# FPGA_IO.net
KiCad netlist of a schematic drawn in Altium Designer
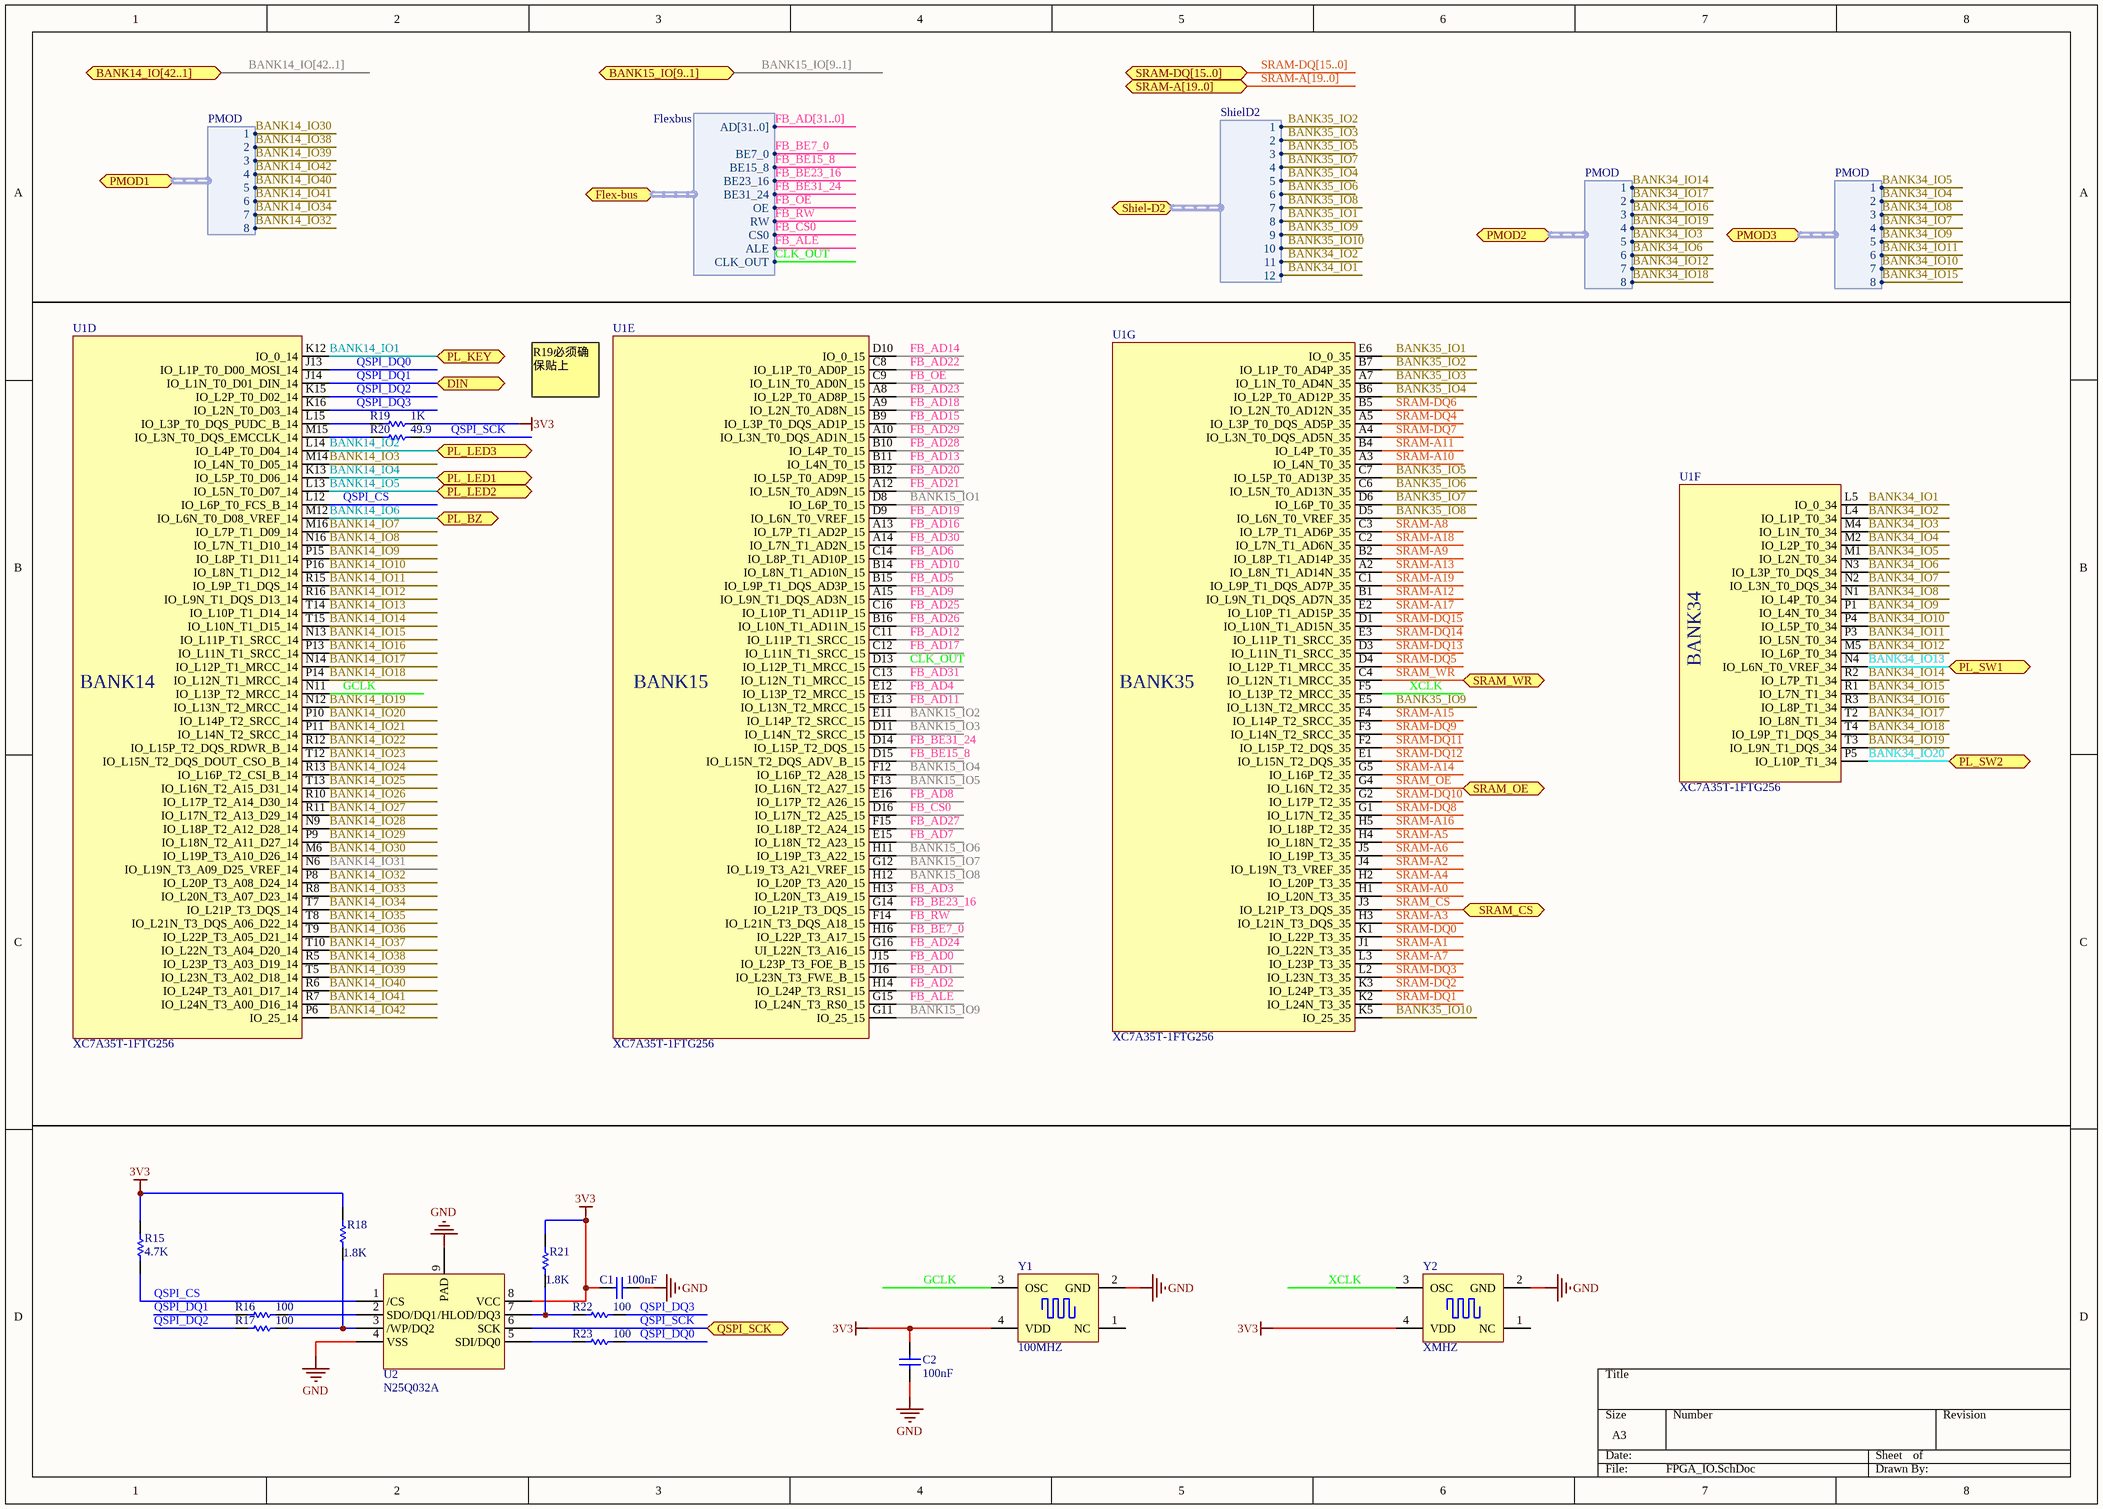
[diagram p0: FPGA_IO.SchDoc]

(export (version "E")
  (design (tool "Eeschema 10.0.6"))
  (components
    (comp (ref "C1")
      (value "100nF")
      (footprint "1608[0603]")
      (description "贴片电容")
      (fields (field (name "Comment") "Cap") (field (name "PUBLISHER") "Altium Limited"))
      (libsource (lib "Sparks") (part "Cap"))
    )
    (comp (ref "C2")
      (value "100nF")
      (footprint "1608[0603]")
      (description "贴片电容")
      (fields (field (name "Comment") "Cap") (field (name "PUBLISHER") "Altium Limited"))
      (libsource (lib "Sparks") (part "Cap"))
    )
    (comp (ref "R15")
      (value "4.7K")
      (footprint "1608[0603]")
      (description "贴片电阻")
      (fields (field (name "Comment") "Res") (field (name "PUBLISHER") "Altium Limited"))
      (libsource (lib "Sparks") (part "Res"))
    )
    (comp (ref "R16")
      (value "100")
      (footprint "1608[0603]")
      (description "贴片电阻")
      (fields (field (name "Comment") "Res") (field (name "PUBLISHER") "Altium Limited"))
      (libsource (lib "Sparks") (part "Res"))
    )
    (comp (ref "R17")
      (value "100")
      (footprint "1608[0603]")
      (description "贴片电阻")
      (fields (field (name "Comment") "Res") (field (name "PUBLISHER") "Altium Limited"))
      (libsource (lib "Sparks") (part "Res"))
    )
    (comp (ref "R18")
      (value "1.8K")
      (footprint "1608[0603]")
      (description "贴片电阻")
      (fields (field (name "Comment") "Res") (field (name "PUBLISHER") "Altium Limited"))
      (libsource (lib "Sparks") (part "Res"))
    )
    (comp (ref "R19")
      (value "1K")
      (footprint "1608[0603]")
      (description "贴片电阻")
      (fields (field (name "Comment") "Res") (field (name "PUBLISHER") "Altium Limited"))
      (libsource (lib "Sparks") (part "Res"))
    )
    (comp (ref "R20")
      (value "49.9")
      (footprint "R2012")
      (description "贴片电阻")
      (fields (field (name "Comment") "Res") (field (name "PUBLISHER") "Altium Limited"))
      (libsource (lib "Sparks") (part "Res"))
    )
    (comp (ref "R21")
      (value "1.8K")
      (footprint "1608[0603]")
      (description "贴片电阻")
      (fields (field (name "Comment") "Res") (field (name "PUBLISHER") "Altium Limited"))
      (libsource (lib "Sparks") (part "Res"))
    )
    (comp (ref "R22")
      (value "100")
      (footprint "1608[0603]")
      (description "贴片电阻")
      (fields (field (name "Comment") "Res") (field (name "PUBLISHER") "Altium Limited"))
      (libsource (lib "Sparks") (part "Res"))
    )
    (comp (ref "R23")
      (value "100")
      (footprint "R2012")
      (description "贴片电阻")
      (fields (field (name "Comment") "Res") (field (name "PUBLISHER") "Altium Limited"))
      (libsource (lib "Sparks") (part "Res"))
    )
    (comp (ref "U1")
      (value "XC7A35T-1FTG256")
      (footprint "BGA100P9X9-81A")
      (libsource (lib "Schlib") (part "XC7A35T-1FTG256"))
    )
    (comp (ref "U2")
      (value "N25Q032A")
      (footprint "QFN127P500X600X100_HS-9N")
      (libsource (lib "2号库") (part "N25Q032A"))
    )
    (comp (ref "Y1") (value "100MHZ") (footprint "XTAL7_3225") (libsource (lib "K60-V4.0") (part "XTAL1")))
    (comp (ref "Y2") (value "XMHZ") (footprint "XTAL7_3225") (libsource (lib "K60-V4.0") (part "XTAL1")))
  )
  (nets
    (net (code "4") (name "/BANK14_IO1") (class "Default")
      (node (ref "U1") (pin "K12") (pinfunction "IO_0_14_K12") (pintype "passive"))
    )
    (net (code "5") (name "/BANK14_IO2") (class "Default")
      (node (ref "U1") (pin "L14") (pinfunction "IO_L4P_T0_D04_14_L14") (pintype "passive"))
    )
    (net (code "6") (name "/BANK14_IO3") (class "Default")
      (node (ref "U1") (pin "M14") (pinfunction "IO_L4N_T0_D05_14_M14") (pintype "passive"))
    )
    (net (code "7") (name "/BANK14_IO4") (class "Default")
      (node (ref "U1") (pin "K13") (pinfunction "IO_L5P_T0_D06_14_K13") (pintype "passive"))
    )
    (net (code "8") (name "/BANK14_IO5") (class "Default")
      (node (ref "U1") (pin "L13") (pinfunction "IO_L5N_T0_D07_14_L13") (pintype "passive"))
    )
    (net (code "9") (name "/BANK14_IO6") (class "Default")
      (node (ref "U1") (pin "M12") (pinfunction "IO_L6N_T0_D08_VREF_14_M12") (pintype "passive"))
    )
    (net (code "10") (name "/BANK14_IO7") (class "Default")
      (node (ref "U1") (pin "M16") (pinfunction "IO_L7P_T1_D09_14_M16") (pintype "passive"))
    )
    (net (code "11") (name "/BANK14_IO8") (class "Default")
      (node (ref "U1") (pin "N16") (pinfunction "IO_L7N_T1_D10_14_N16") (pintype "passive"))
    )
    (net (code "12") (name "/BANK14_IO9") (class "Default")
      (node (ref "U1") (pin "P15") (pinfunction "IO_L8P_T1_D11_14_P15") (pintype "passive"))
    )
    (net (code "13") (name "/BANK14_IO10") (class "Default")
      (node (ref "U1") (pin "P16") (pinfunction "IO_L8N_T1_D12_14_P16") (pintype "passive"))
    )
    (net (code "14") (name "/BANK14_IO11") (class "Default")
      (node (ref "U1") (pin "R15") (pinfunction "IO_L9P_T1_DQS_14_R15") (pintype "passive"))
    )
    (net (code "15") (name "/BANK14_IO12") (class "Default")
      (node (ref "U1") (pin "R16") (pinfunction "IO_L9N_T1_DQS_D13_14_R16") (pintype "passive"))
    )
    (net (code "16") (name "/BANK14_IO13") (class "Default")
      (node (ref "U1") (pin "T14") (pinfunction "IO_L10P_T1_D14_14_T14") (pintype "passive"))
    )
    (net (code "17") (name "/BANK14_IO14") (class "Default")
      (node (ref "U1") (pin "T15") (pinfunction "IO_L10N_T1_D15_14_T15") (pintype "passive"))
    )
    (net (code "18") (name "/BANK14_IO15") (class "Default")
      (node (ref "U1") (pin "N13") (pinfunction "IO_L11P_T1_SRCC_14_N13") (pintype "passive"))
    )
    (net (code "19") (name "/BANK14_IO16") (class "Default")
      (node (ref "U1") (pin "P13") (pinfunction "IO_L11N_T1_SRCC_14_P13") (pintype "passive"))
    )
    (net (code "20") (name "/BANK14_IO17") (class "Default")
      (node (ref "U1") (pin "N14") (pinfunction "IO_L12P_T1_MRCC_14_N14") (pintype "passive"))
    )
    (net (code "21") (name "/BANK14_IO18") (class "Default")
      (node (ref "U1") (pin "P14") (pinfunction "IO_L12N_T1_MRCC_14_P14") (pintype "passive"))
    )
    (net (code "22") (name "/BANK14_IO19") (class "Default")
      (node (ref "U1") (pin "N12") (pinfunction "IO_L13N_T2_MRCC_14_N12") (pintype "passive"))
    )
    (net (code "23") (name "/BANK14_IO20") (class "Default")
      (node (ref "U1") (pin "P10") (pinfunction "IO_L14P_T2_SRCC_14_P10") (pintype "passive"))
    )
    (net (code "24") (name "/BANK14_IO21") (class "Default")
      (node (ref "U1") (pin "P11") (pinfunction "IO_L14N_T2_SRCC_14_P11") (pintype "passive"))
    )
    (net (code "25") (name "/BANK14_IO22") (class "Default")
      (node (ref "U1") (pin "R12") (pinfunction "IO_L15P_T2_DQS_RDWR_B_14_R12") (pintype "passive"))
    )
    (net (code "26") (name "/BANK14_IO23") (class "Default")
      (node (ref "U1") (pin "T12") (pinfunction "IO_L15N_T2_DQS_DOUT_CSO_B_14_T12") (pintype "passive"))
    )
    (net (code "27") (name "/BANK14_IO24") (class "Default")
      (node (ref "U1") (pin "R13") (pinfunction "IO_L16P_T2_CSI_B_14_R13") (pintype "passive"))
    )
    (net (code "28") (name "/BANK14_IO25") (class "Default")
      (node (ref "U1") (pin "T13") (pinfunction "IO_L16N_T2_A15_D31_14_T13") (pintype "passive"))
    )
    (net (code "29") (name "/BANK14_IO26") (class "Default")
      (node (ref "U1") (pin "R10") (pinfunction "IO_L17P_T2_A14_D30_14_R10") (pintype "passive"))
    )
    (net (code "30") (name "/BANK14_IO27") (class "Default")
      (node (ref "U1") (pin "R11") (pinfunction "IO_L17N_T2_A13_D29_14_R11") (pintype "passive"))
    )
    (net (code "31") (name "/BANK14_IO28") (class "Default")
      (node (ref "U1") (pin "N9") (pinfunction "IO_L18P_T2_A12_D28_14_N9") (pintype "passive"))
    )
    (net (code "32") (name "/BANK14_IO29") (class "Default")
      (node (ref "U1") (pin "P9") (pinfunction "IO_L18N_T2_A11_D27_14_P9") (pintype "passive"))
    )
    (net (code "33") (name "/BANK14_IO30") (class "Default")
      (node (ref "U1") (pin "M6") (pinfunction "IO_L19P_T3_A10_D26_14_M6") (pintype "passive"))
    )
    (net (code "34") (name "/BANK14_IO31") (class "Default")
      (node (ref "U1") (pin "N6") (pinfunction "IO_L19N_T3_A09_D25_VREF_14_N6") (pintype "passive"))
    )
    (net (code "35") (name "/BANK14_IO32") (class "Default")
      (node (ref "U1") (pin "P8") (pinfunction "IO_L20P_T3_A08_D24_14_P8") (pintype "passive"))
    )
    (net (code "36") (name "/BANK14_IO33") (class "Default")
      (node (ref "U1") (pin "R8") (pinfunction "IO_L20N_T3_A07_D23_14_R8") (pintype "passive"))
    )
    (net (code "37") (name "/BANK14_IO34") (class "Default")
      (node (ref "U1") (pin "T7") (pinfunction "IO_L21P_T3_DQS_14_T7") (pintype "passive"))
    )
    (net (code "38") (name "/BANK14_IO35") (class "Default")
      (node (ref "U1") (pin "T8") (pinfunction "IO_L21N_T3_DQS_A06_D22_14_T8") (pintype "passive"))
    )
    (net (code "39") (name "/BANK14_IO36") (class "Default")
      (node (ref "U1") (pin "T9") (pinfunction "IO_L22P_T3_A05_D21_14_T9") (pintype "passive"))
    )
    (net (code "40") (name "/BANK14_IO37") (class "Default")
      (node (ref "U1") (pin "T10") (pinfunction "IO_L22N_T3_A04_D20_14_T10") (pintype "passive"))
    )
    (net (code "41") (name "/BANK14_IO38") (class "Default")
      (node (ref "U1") (pin "R5") (pinfunction "IO_L23P_T3_A03_D19_14_R5") (pintype "passive"))
    )
    (net (code "42") (name "/BANK14_IO39") (class "Default")
      (node (ref "U1") (pin "T5") (pinfunction "IO_L23N_T3_A02_D18_14_T5") (pintype "passive"))
    )
    (net (code "43") (name "/BANK14_IO40") (class "Default")
      (node (ref "U1") (pin "R6") (pinfunction "IO_L24P_T3_A01_D17_14_R6") (pintype "passive"))
    )
    (net (code "44") (name "/BANK14_IO41") (class "Default")
      (node (ref "U1") (pin "R7") (pinfunction "IO_L24N_T3_A00_D16_14_R7") (pintype "passive"))
    )
    (net (code "45") (name "/BANK14_IO42") (class "Default")
      (node (ref "U1") (pin "P6") (pinfunction "IO_25_14_P6") (pintype "passive"))
    )
    (net (code "47") (name "/BANK15_IO1") (class "Default")
      (node (ref "U1") (pin "D8") (pinfunction "IO_L6P_T0_15_D8") (pintype "passive"))
    )
    (net (code "48") (name "/BANK15_IO2") (class "Default")
      (node (ref "U1") (pin "E11") (pinfunction "IO_L14P_T2_SRCC_15_E11") (pintype "passive"))
    )
    (net (code "49") (name "/BANK15_IO3") (class "Default")
      (node (ref "U1") (pin "D11") (pinfunction "IO_L14N_T2_SRCC_15_D11") (pintype "passive"))
    )
    (net (code "50") (name "/BANK15_IO4") (class "Default")
      (node (ref "U1") (pin "F12") (pinfunction "IO_L16P_T2_A28_15_F12") (pintype "passive"))
    )
    (net (code "51") (name "/BANK15_IO5") (class "Default")
      (node (ref "U1") (pin "F13") (pinfunction "IO_L16N_T2_A27_15_F13") (pintype "passive"))
    )
    (net (code "52") (name "/BANK15_IO6") (class "Default")
      (node (ref "U1") (pin "H11") (pinfunction "IO_L19P_T3_A22_15_H11") (pintype "passive"))
    )
    (net (code "53") (name "/BANK15_IO7") (class "Default")
      (node (ref "U1") (pin "G12") (pinfunction "IO_L19_T3_A21_VREF_15_G12") (pintype "passive"))
    )
    (net (code "54") (name "/BANK15_IO8") (class "Default")
      (node (ref "U1") (pin "H12") (pinfunction "IO_L20P_T3_A20_15_H12") (pintype "passive"))
    )
    (net (code "55") (name "/BANK15_IO9") (class "Default")
      (node (ref "U1") (pin "G11") (pinfunction "IO_25_15_G11") (pintype "passive"))
    )
    (net (code "57") (name "/BANK34_IO1") (class "Default")
      (node (ref "U1") (pin "L5") (pinfunction "IO_0_34_L5") (pintype "passive"))
    )
    (net (code "58") (name "/BANK34_IO2") (class "Default")
      (node (ref "U1") (pin "L4") (pinfunction "IO_L1P_T0_34_L4") (pintype "passive"))
    )
    (net (code "59") (name "/BANK34_IO3") (class "Default")
      (node (ref "U1") (pin "M4") (pinfunction "IO_L1N_T0_34_M4") (pintype "passive"))
    )
    (net (code "60") (name "/BANK34_IO4") (class "Default")
      (node (ref "U1") (pin "M2") (pinfunction "IO_L2P_T0_34_M2") (pintype "passive"))
    )
    (net (code "61") (name "/BANK34_IO5") (class "Default")
      (node (ref "U1") (pin "M1") (pinfunction "IO_L2N_T0_34_M1") (pintype "passive"))
    )
    (net (code "62") (name "/BANK34_IO6") (class "Default")
      (node (ref "U1") (pin "N3") (pinfunction "IO_L3P_T0_DQS_34_N3") (pintype "passive"))
    )
    (net (code "63") (name "/BANK34_IO7") (class "Default")
      (node (ref "U1") (pin "N2") (pinfunction "IO_L3N_T0_DQS_34_N2") (pintype "passive"))
    )
    (net (code "64") (name "/BANK34_IO8") (class "Default")
      (node (ref "U1") (pin "N1") (pinfunction "IO_L4P_T0_34_N1") (pintype "passive"))
    )
    (net (code "65") (name "/BANK34_IO9") (class "Default")
      (node (ref "U1") (pin "P1") (pinfunction "IO_L4N_T0_34_P1") (pintype "passive"))
    )
    (net (code "66") (name "/BANK34_IO10") (class "Default")
      (node (ref "U1") (pin "P4") (pinfunction "IO_L5P_T0_34_P4") (pintype "passive"))
    )
    (net (code "67") (name "/BANK34_IO11") (class "Default")
      (node (ref "U1") (pin "P3") (pinfunction "IO_L5N_T0_34_P3") (pintype "passive"))
    )
    (net (code "68") (name "/BANK34_IO12") (class "Default")
      (node (ref "U1") (pin "M5") (pinfunction "IO_L6P_T0_34_M5") (pintype "passive"))
    )
    (net (code "69") (name "/BANK34_IO13") (class "Default")
      (node (ref "U1") (pin "N4") (pinfunction "IO_L6N_T0_VREF_34_N4") (pintype "passive"))
    )
    (net (code "70") (name "/BANK34_IO14") (class "Default")
      (node (ref "U1") (pin "R2") (pinfunction "IO_L7P_T1_34_R2") (pintype "passive"))
    )
    (net (code "71") (name "/BANK34_IO15") (class "Default")
      (node (ref "U1") (pin "R1") (pinfunction "IO_L7N_T1_34_R1") (pintype "passive"))
    )
    (net (code "72") (name "/BANK34_IO16") (class "Default")
      (node (ref "U1") (pin "R3") (pinfunction "IO_L8P_T1_34_R3") (pintype "passive"))
    )
    (net (code "73") (name "/BANK34_IO17") (class "Default")
      (node (ref "U1") (pin "T2") (pinfunction "IO_L8N_T1_34_T2") (pintype "passive"))
    )
    (net (code "74") (name "/BANK34_IO18") (class "Default")
      (node (ref "U1") (pin "T4") (pinfunction "IO_L9P_T1_DQS_34_T4") (pintype "passive"))
    )
    (net (code "75") (name "/BANK34_IO19") (class "Default")
      (node (ref "U1") (pin "T3") (pinfunction "IO_L9N_T1_DQS_34_T3") (pintype "passive"))
    )
    (net (code "76") (name "/BANK34_IO20") (class "Default")
      (node (ref "U1") (pin "P5") (pinfunction "IO_L10P_T1_34_P5") (pintype "passive"))
    )
    (net (code "77") (name "/BANK35_IO1") (class "Default")
      (node (ref "U1") (pin "E6") (pinfunction "IO_0_35_E6") (pintype "passive"))
    )
    (net (code "78") (name "/BANK35_IO2") (class "Default")
      (node (ref "U1") (pin "B7") (pinfunction "IO_L1P_T0_AD4P_35_B7") (pintype "passive"))
    )
    (net (code "79") (name "/BANK35_IO3") (class "Default")
      (node (ref "U1") (pin "A7") (pinfunction "IO_L1N_T0_AD4N_35_A7") (pintype "passive"))
    )
    (net (code "80") (name "/BANK35_IO4") (class "Default")
      (node (ref "U1") (pin "B6") (pinfunction "IO_L2P_T0_AD12P_35_B6") (pintype "passive"))
    )
    (net (code "81") (name "/BANK35_IO5") (class "Default")
      (node (ref "U1") (pin "C7") (pinfunction "IO_L5P_T0_AD13P_35_C7") (pintype "passive"))
    )
    (net (code "82") (name "/BANK35_IO6") (class "Default")
      (node (ref "U1") (pin "C6") (pinfunction "IO_L5N_T0_AD13N_35_C6") (pintype "passive"))
    )
    (net (code "83") (name "/BANK35_IO7") (class "Default")
      (node (ref "U1") (pin "D6") (pinfunction "IO_L6P_T0_35_D6") (pintype "passive"))
    )
    (net (code "84") (name "/BANK35_IO8") (class "Default")
      (node (ref "U1") (pin "D5") (pinfunction "IO_L6N_T0_VREF_35_D5") (pintype "passive"))
    )
    (net (code "85") (name "/BANK35_IO9") (class "Default")
      (node (ref "U1") (pin "E5") (pinfunction "IO_L13N_T2_MRCC_35_E5") (pintype "passive"))
    )
    (net (code "86") (name "/BANK35_IO10") (class "Default")
      (node (ref "U1") (pin "K5") (pinfunction "IO_25_35_K5") (pintype "passive"))
    )
    (net (code "87") (name "/CLK_OUT") (class "Default")
      (node (ref "U1") (pin "D13") (pinfunction "IO_L12P_T1_MRCC_15_D13") (pintype "passive"))
    )
    (net (code "88") (name "/FB_AD0") (class "Default")
      (node (ref "U1") (pin "J15") (pinfunction "IO_L23P_T3_FOE_B_15_J15") (pintype "passive"))
    )
    (net (code "89") (name "/FB_AD1") (class "Default")
      (node (ref "U1") (pin "J16") (pinfunction "IO_L23N_T3_FWE_B_15_J16") (pintype "passive"))
    )
    (net (code "90") (name "/FB_AD2") (class "Default")
      (node (ref "U1") (pin "H14") (pinfunction "IO_L24P_T3_RS1_15_H14") (pintype "passive"))
    )
    (net (code "91") (name "/FB_AD3") (class "Default")
      (node (ref "U1") (pin "H13") (pinfunction "IO_L20N_T3_A19_15_H13") (pintype "passive"))
    )
    (net (code "92") (name "/FB_AD4") (class "Default")
      (node (ref "U1") (pin "E12") (pinfunction "IO_L13P_T2_MRCC_15_E12") (pintype "passive"))
    )
    (net (code "93") (name "/FB_AD5") (class "Default")
      (node (ref "U1") (pin "B15") (pinfunction "IO_L9P_T1_DQS_AD3P_15_B15") (pintype "passive"))
    )
    (net (code "94") (name "/FB_AD6") (class "Default")
      (node (ref "U1") (pin "C14") (pinfunction "IO_L8P_T1_AD10P_15_C14") (pintype "passive"))
    )
    (net (code "95") (name "/FB_AD7") (class "Default")
      (node (ref "U1") (pin "E15") (pinfunction "IO_L18N_T2_A23_15_E15") (pintype "passive"))
    )
    (net (code "96") (name "/FB_AD8") (class "Default")
      (node (ref "U1") (pin "E16") (pinfunction "IO_L17P_T2_A26_15_E16") (pintype "passive"))
    )
    (net (code "97") (name "/FB_AD9") (class "Default")
      (node (ref "U1") (pin "A15") (pinfunction "IO_L9N_T1_DQS_AD3N_15_A15") (pintype "passive"))
    )
    (net (code "98") (name "/FB_AD10") (class "Default")
      (node (ref "U1") (pin "B14") (pinfunction "IO_L8N_T1_AD10N_15_B14") (pintype "passive"))
    )
    (net (code "99") (name "/FB_AD11") (class "Default")
      (node (ref "U1") (pin "E13") (pinfunction "IO_L13N_T2_MRCC_15_E13") (pintype "passive"))
    )
    (net (code "100") (name "/FB_AD12") (class "Default")
      (node (ref "U1") (pin "C11") (pinfunction "IO_L11P_T1_SRCC_15_C11") (pintype "passive"))
    )
    (net (code "101") (name "/FB_AD13") (class "Default")
      (node (ref "U1") (pin "B11") (pinfunction "IO_L4N_T0_15_B11") (pintype "passive"))
    )
    (net (code "102") (name "/FB_AD14") (class "Default")
      (node (ref "U1") (pin "D10") (pinfunction "IO_0_15_D10") (pintype "passive"))
    )
    (net (code "103") (name "/FB_AD15") (class "Default")
      (node (ref "U1") (pin "B9") (pinfunction "IO_L3P_T0_DQS_AD1P_15_B9") (pintype "passive"))
    )
    (net (code "104") (name "/FB_AD16") (class "Default")
      (node (ref "U1") (pin "A13") (pinfunction "IO_L7P_T1_AD2P_15_A13") (pintype "passive"))
    )
    (net (code "105") (name "/FB_AD17") (class "Default")
      (node (ref "U1") (pin "C12") (pinfunction "IO_L11N_T1_SRCC_15_C12") (pintype "passive"))
    )
    (net (code "106") (name "/FB_AD18") (class "Default")
      (node (ref "U1") (pin "A9") (pinfunction "IO_L2N_T0_AD8N_15_A9") (pintype "passive"))
    )
    (net (code "107") (name "/FB_AD19") (class "Default")
      (node (ref "U1") (pin "D9") (pinfunction "IO_L6N_T0_VREF_15_D9") (pintype "passive"))
    )
    (net (code "108") (name "/FB_AD20") (class "Default")
      (node (ref "U1") (pin "B12") (pinfunction "IO_L5P_T0_AD9P_15_B12") (pintype "passive"))
    )
    (net (code "109") (name "/FB_AD21") (class "Default")
      (node (ref "U1") (pin "A12") (pinfunction "IO_L5N_T0_AD9N_15_A12") (pintype "passive"))
    )
    (net (code "110") (name "/FB_AD22") (class "Default")
      (node (ref "U1") (pin "C8") (pinfunction "IO_L1P_T0_AD0P_15_C8") (pintype "passive"))
    )
    (net (code "111") (name "/FB_AD23") (class "Default")
      (node (ref "U1") (pin "A8") (pinfunction "IO_L2P_T0_AD8P_15_A8") (pintype "passive"))
    )
    (net (code "112") (name "/FB_AD24") (class "Default")
      (node (ref "U1") (pin "G16") (pinfunction "UI_L22N_T3_A16_15_G16") (pintype "passive"))
    )
    (net (code "113") (name "/FB_AD25") (class "Default")
      (node (ref "U1") (pin "C16") (pinfunction "IO_L10P_T1_AD11P_15_C16") (pintype "passive"))
    )
    (net (code "114") (name "/FB_AD26") (class "Default")
      (node (ref "U1") (pin "B16") (pinfunction "IO_L10N_T1_AD11N_15_B16") (pintype "passive"))
    )
    (net (code "115") (name "/FB_AD27") (class "Default")
      (node (ref "U1") (pin "F15") (pinfunction "IO_L18P_T2_A24_15_F15") (pintype "passive"))
    )
    (net (code "116") (name "/FB_AD28") (class "Default")
      (node (ref "U1") (pin "B10") (pinfunction "IO_L4P_T0_15_B10") (pintype "passive"))
    )
    (net (code "117") (name "/FB_AD29") (class "Default")
      (node (ref "U1") (pin "A10") (pinfunction "IO_L3N_T0_DQS_AD1N_15_A10") (pintype "passive"))
    )
    (net (code "118") (name "/FB_AD30") (class "Default")
      (node (ref "U1") (pin "A14") (pinfunction "IO_L7N_T1_AD2N_15_A14") (pintype "passive"))
    )
    (net (code "119") (name "/FB_AD31") (class "Default")
      (node (ref "U1") (pin "C13") (pinfunction "IO_L12N_T1_MRCC_15_C13") (pintype "passive"))
    )
    (net (code "120") (name "/FB_ALE") (class "Default")
      (node (ref "U1") (pin "G15") (pinfunction "IO_L24N_T3_RS0_15_G15") (pintype "passive"))
    )
    (net (code "121") (name "/FB_BE7_0") (class "Default")
      (node (ref "U1") (pin "H16") (pinfunction "IO_L22P_T3_A17_15_H16") (pintype "passive"))
    )
    (net (code "122") (name "/FB_BE15_8") (class "Default")
      (node (ref "U1") (pin "D15") (pinfunction "IO_L15N_T2_DQS_ADV_B_15_D15") (pintype "passive"))
    )
    (net (code "123") (name "/FB_BE23_16") (class "Default")
      (node (ref "U1") (pin "G14") (pinfunction "IO_L21P_T3_DQS_15_G14") (pintype "passive"))
    )
    (net (code "124") (name "/FB_BE31_24") (class "Default")
      (node (ref "U1") (pin "D14") (pinfunction "IO_L15P_T2_DQS_15_D14") (pintype "passive"))
    )
    (net (code "125") (name "/FB_CS0") (class "Default")
      (node (ref "U1") (pin "D16") (pinfunction "IO_L17N_T2_A25_15_D16") (pintype "passive"))
    )
    (net (code "126") (name "/FB_OE") (class "Default")
      (node (ref "U1") (pin "C9") (pinfunction "IO_L1N_T0_AD0N_15_C9") (pintype "passive"))
    )
    (net (code "127") (name "/FB_RW") (class "Default")
      (node (ref "U1") (pin "F14") (pinfunction "IO_L21N_T3_DQS_A18_15_F14") (pintype "passive"))
    )
    (net (code "129") (name "/GCLK") (class "Default")
      (node (ref "U1") (pin "N11") (pinfunction "IO_L13P_T2_MRCC_14_N11") (pintype "passive"))
      (node (ref "Y1") (pin "3") (pinfunction "OSC_3") (pintype "passive"))
    )
    (net (code "130") (name "/QSPI_CS") (class "Default")
      (node (ref "R15") (pin "2") (pinfunction "2_2") (pintype "passive"))
      (node (ref "U1") (pin "L12") (pinfunction "IO_L6P_T0_FCS_B_14_L12") (pintype "passive"))
      (node (ref "U2") (pin "1") (pinfunction "/CS_1") (pintype "passive"))
    )
    (net (code "131") (name "/QSPI_DQ0") (class "Default")
      (node (ref "R23") (pin "1") (pinfunction "1_1") (pintype "passive"))
      (node (ref "U1") (pin "J13") (pinfunction "IO_L1P_T0_D00_MOSI_14_J13") (pintype "passive"))
    )
    (net (code "132") (name "/QSPI_DQ1") (class "Default")
      (node (ref "R16") (pin "2") (pinfunction "2_2") (pintype "passive"))
      (node (ref "U1") (pin "J14") (pinfunction "IO_L1N_T0_D01_DIN_14_J14") (pintype "passive"))
    )
    (net (code "133") (name "/QSPI_DQ2") (class "Default")
      (node (ref "R17") (pin "2") (pinfunction "2_2") (pintype "passive"))
      (node (ref "U1") (pin "K15") (pinfunction "IO_L2P_T0_D02_14_K15") (pintype "passive"))
    )
    (net (code "134") (name "/QSPI_DQ3") (class "Default")
      (node (ref "R22") (pin "1") (pinfunction "1_1") (pintype "passive"))
      (node (ref "U1") (pin "K16") (pinfunction "IO_L2N_T0_D03_14_K16") (pintype "passive"))
    )
    (net (code "135") (name "/QSPI_SCK") (class "Default")
      (node (ref "R20") (pin "1") (pinfunction "1_1") (pintype "passive"))
      (node (ref "U2") (pin "6") (pinfunction "SCK_6") (pintype "passive"))
    )
    (net (code "136") (name "/SRAM-A0") (class "Default")
      (node (ref "U1") (pin "H1") (pinfunction "IO_L20N_T3_35_H1") (pintype "passive"))
    )
    (net (code "137") (name "/SRAM-A1") (class "Default")
      (node (ref "U1") (pin "J1") (pinfunction "IO_L22N_T3_35_J1") (pintype "passive"))
    )
    (net (code "138") (name "/SRAM-A2") (class "Default")
      (node (ref "U1") (pin "J4") (pinfunction "IO_L19N_T3_VREF_35_J4") (pintype "passive"))
    )
    (net (code "139") (name "/SRAM-A3") (class "Default")
      (node (ref "U1") (pin "H3") (pinfunction "IO_L21N_T3_DQS_35_H3") (pintype "passive"))
    )
    (net (code "140") (name "/SRAM-A4") (class "Default")
      (node (ref "U1") (pin "H2") (pinfunction "IO_L20P_T3_35_H2") (pintype "passive"))
    )
    (net (code "141") (name "/SRAM-A5") (class "Default")
      (node (ref "U1") (pin "H4") (pinfunction "IO_L18N_T2_35_H4") (pintype "passive"))
    )
    (net (code "142") (name "/SRAM-A6") (class "Default")
      (node (ref "U1") (pin "J5") (pinfunction "IO_L19P_T3_35_J5") (pintype "passive"))
    )
    (net (code "143") (name "/SRAM-A7") (class "Default")
      (node (ref "U1") (pin "L3") (pinfunction "IO_L23P_T3_35_L3") (pintype "passive"))
    )
    (net (code "144") (name "/SRAM-A8") (class "Default")
      (node (ref "U1") (pin "C3") (pinfunction "IO_L7P_T1_AD6P_35_C3") (pintype "passive"))
    )
    (net (code "145") (name "/SRAM-A9") (class "Default")
      (node (ref "U1") (pin "B2") (pinfunction "IO_L8P_T1_AD14P_35_B2") (pintype "passive"))
    )
    (net (code "146") (name "/SRAM-A10") (class "Default")
      (node (ref "U1") (pin "A3") (pinfunction "IO_L4N_T0_35_A3") (pintype "passive"))
    )
    (net (code "147") (name "/SRAM-A11") (class "Default")
      (node (ref "U1") (pin "B4") (pinfunction "IO_L4P_T0_35_B4") (pintype "passive"))
    )
    (net (code "148") (name "/SRAM-A12") (class "Default")
      (node (ref "U1") (pin "B1") (pinfunction "IO_L9N_T1_DQS_AD7N_35_B1") (pintype "passive"))
    )
    (net (code "149") (name "/SRAM-A13") (class "Default")
      (node (ref "U1") (pin "A2") (pinfunction "IO_L8N_T1_AD14N_35_A2") (pintype "passive"))
    )
    (net (code "150") (name "/SRAM-A14") (class "Default")
      (node (ref "U1") (pin "G5") (pinfunction "IO_L16P_T2_35_G5") (pintype "passive"))
    )
    (net (code "151") (name "/SRAM-A15") (class "Default")
      (node (ref "U1") (pin "F4") (pinfunction "IO_L14P_T2_SRCC_35_F4") (pintype "passive"))
    )
    (net (code "152") (name "/SRAM-A16") (class "Default")
      (node (ref "U1") (pin "H5") (pinfunction "IO_L18P_T2_35_H5") (pintype "passive"))
    )
    (net (code "153") (name "/SRAM-A17") (class "Default")
      (node (ref "U1") (pin "E2") (pinfunction "IO_L10P_T1_AD15P_35_E2") (pintype "passive"))
    )
    (net (code "154") (name "/SRAM-A18") (class "Default")
      (node (ref "U1") (pin "C2") (pinfunction "IO_L7N_T1_AD6N_35_C2") (pintype "passive"))
    )
    (net (code "155") (name "/SRAM-A19") (class "Default")
      (node (ref "U1") (pin "C1") (pinfunction "IO_L9P_T1_DQS_AD7P_35_C1") (pintype "passive"))
    )
    (net (code "157") (name "/SRAM-DQ0") (class "Default")
      (node (ref "U1") (pin "K1") (pinfunction "IO_L22P_T3_35_K1") (pintype "passive"))
    )
    (net (code "158") (name "/SRAM-DQ1") (class "Default")
      (node (ref "U1") (pin "K2") (pinfunction "IO_L24N_T3_35_K2") (pintype "passive"))
    )
    (net (code "159") (name "/SRAM-DQ2") (class "Default")
      (node (ref "U1") (pin "K3") (pinfunction "IO_L24P_T3_35_K3") (pintype "passive"))
    )
    (net (code "160") (name "/SRAM-DQ3") (class "Default")
      (node (ref "U1") (pin "L2") (pinfunction "IO_L23N_T3_35_L2") (pintype "passive"))
    )
    (net (code "161") (name "/SRAM-DQ4") (class "Default")
      (node (ref "U1") (pin "A5") (pinfunction "IO_L3P_T0_DQS_AD5P_35_A5") (pintype "passive"))
    )
    (net (code "162") (name "/SRAM-DQ5") (class "Default")
      (node (ref "U1") (pin "D4") (pinfunction "IO_L12P_T1_MRCC_35_D4") (pintype "passive"))
    )
    (net (code "163") (name "/SRAM-DQ6") (class "Default")
      (node (ref "U1") (pin "B5") (pinfunction "IO_L2N_T0_AD12N_35_B5") (pintype "passive"))
    )
    (net (code "164") (name "/SRAM-DQ7") (class "Default")
      (node (ref "U1") (pin "A4") (pinfunction "IO_L3N_T0_DQS_AD5N_35_A4") (pintype "passive"))
    )
    (net (code "165") (name "/SRAM-DQ8") (class "Default")
      (node (ref "U1") (pin "G1") (pinfunction "IO_L17N_T2_35_G1") (pintype "passive"))
    )
    (net (code "166") (name "/SRAM-DQ9") (class "Default")
      (node (ref "U1") (pin "F3") (pinfunction "IO_L14N_T2_SRCC_35_F3") (pintype "passive"))
    )
    (net (code "167") (name "/SRAM-DQ10") (class "Default")
      (node (ref "U1") (pin "G2") (pinfunction "IO_L17P_T2_35_G2") (pintype "passive"))
    )
    (net (code "168") (name "/SRAM-DQ11") (class "Default")
      (node (ref "U1") (pin "F2") (pinfunction "IO_L15P_T2_DQS_35_F2") (pintype "passive"))
    )
    (net (code "169") (name "/SRAM-DQ12") (class "Default")
      (node (ref "U1") (pin "E1") (pinfunction "IO_L15N_T2_DQS_35_E1") (pintype "passive"))
    )
    (net (code "170") (name "/SRAM-DQ13") (class "Default")
      (node (ref "U1") (pin "D3") (pinfunction "IO_L11N_T1_SRCC_35_D3") (pintype "passive"))
    )
    (net (code "171") (name "/SRAM-DQ14") (class "Default")
      (node (ref "U1") (pin "E3") (pinfunction "IO_L11P_T1_SRCC_35_E3") (pintype "passive"))
    )
    (net (code "172") (name "/SRAM-DQ15") (class "Default")
      (node (ref "U1") (pin "D1") (pinfunction "IO_L10N_T1_AD15N_35_D1") (pintype "passive"))
    )
    (net (code "174") (name "/SRAM_CS") (class "Default")
      (node (ref "U1") (pin "J3") (pinfunction "IO_L21P_T3_DQS_35_J3") (pintype "passive"))
    )
    (net (code "175") (name "/SRAM_OE") (class "Default")
      (node (ref "U1") (pin "G4") (pinfunction "IO_L16N_T2_35_G4") (pintype "passive"))
    )
    (net (code "176") (name "/SRAM_WR") (class "Default")
      (node (ref "U1") (pin "C4") (pinfunction "IO_L12N_T1_MRCC_35_C4") (pintype "passive"))
    )
    (net (code "177") (name "/XCLK") (class "Default")
      (node (ref "U1") (pin "F5") (pinfunction "IO_L13P_T2_MRCC_35_F5") (pintype "passive"))
      (node (ref "Y2") (pin "3") (pinfunction "OSC_3") (pintype "passive"))
    )
    (net (code "181") (name "3V3") (class "Default")
      (node (ref "C1") (pin "1") (pinfunction "1_1") (pintype "passive"))
      (node (ref "C2") (pin "2") (pinfunction "2_2") (pintype "passive"))
      (node (ref "R15") (pin "1") (pinfunction "1_1") (pintype "passive"))
      (node (ref "R18") (pin "1") (pinfunction "1_1") (pintype "passive"))
      (node (ref "R19") (pin "1") (pinfunction "1_1") (pintype "passive"))
      (node (ref "R21") (pin "1") (pinfunction "1_1") (pintype "passive"))
      (node (ref "U2") (pin "8") (pinfunction "VCC_8") (pintype "passive"))
      (node (ref "Y1") (pin "4") (pinfunction "VDD_4") (pintype "passive"))
      (node (ref "Y2") (pin "4") (pinfunction "VDD_4") (pintype "passive"))
    )
    (net (code "182") (name "GND") (class "Default")
      (node (ref "C1") (pin "2") (pinfunction "2_2") (pintype "passive"))
      (node (ref "C2") (pin "1") (pinfunction "1_1") (pintype "passive"))
      (node (ref "U2") (pin "4") (pinfunction "VSS_4") (pintype "passive"))
      (node (ref "U2") (pin "9") (pinfunction "PAD_9") (pintype "passive"))
      (node (ref "Y1") (pin "2") (pinfunction "GND_2") (pintype "passive"))
      (node (ref "Y2") (pin "2") (pinfunction "GND_2") (pintype "passive"))
    )
    (net (code "183") (name "Net-(U1D-IO_L3N_T0_DQS_EMCCLK_14)") (class "Default")
      (node (ref "R20") (pin "2") (pinfunction "2_2") (pintype "passive"))
      (node (ref "U1") (pin "M15") (pinfunction "IO_L3N_T0_DQS_EMCCLK_14_M15") (pintype "passive"))
    )
    (net (code "184") (name "Net-(U1D-IO_L3P_T0_DQS_PUDC_B_14)") (class "Default")
      (node (ref "R19") (pin "2") (pinfunction "2_2") (pintype "passive"))
      (node (ref "U1") (pin "L15") (pinfunction "IO_L3P_T0_DQS_PUDC_B_14_L15") (pintype "passive"))
    )
    (net (code "185") (name "Net-(U2-SDI{slash}DQ0)") (class "Default")
      (node (ref "R23") (pin "2") (pinfunction "2_2") (pintype "passive"))
      (node (ref "U2") (pin "5") (pinfunction "SDI/DQ0_5") (pintype "passive"))
    )
    (net (code "186") (name "Net-(U2-SDO{slash}DQ1)") (class "Default")
      (node (ref "R16") (pin "1") (pinfunction "1_1") (pintype "passive"))
      (node (ref "U2") (pin "2") (pinfunction "SDO/DQ1_2") (pintype "passive"))
    )
    (net (code "187") (name "Net-(U2-{slash}HLOD{slash}DQ3)") (class "Default")
      (node (ref "R21") (pin "2") (pinfunction "2_2") (pintype "passive"))
      (node (ref "R22") (pin "2") (pinfunction "2_2") (pintype "passive"))
      (node (ref "U2") (pin "7") (pinfunction "/HLOD/DQ3_7") (pintype "passive"))
    )
    (net (code "188") (name "Net-(U2-{slash}WP{slash}DQ2)") (class "Default")
      (node (ref "R17") (pin "1") (pinfunction "1_1") (pintype "passive"))
      (node (ref "R18") (pin "2") (pinfunction "2_2") (pintype "passive"))
      (node (ref "U2") (pin "3") (pinfunction "/WP/DQ2_3") (pintype "passive"))
    )
    (net (code "189") (name "unconnected-(Y1-NC-Pad1)") (class "Default")
      (node (ref "Y1") (pin "1") (pinfunction "NC_1") (pintype "passive"))
    )
    (net (code "190") (name "unconnected-(Y2-NC-Pad1)") (class "Default")
      (node (ref "Y2") (pin "1") (pinfunction "NC_1") (pintype "passive"))
    )
  )
)
